# Processor_Interface.net
KiCad netlist of a schematic drawn in Altium Designer
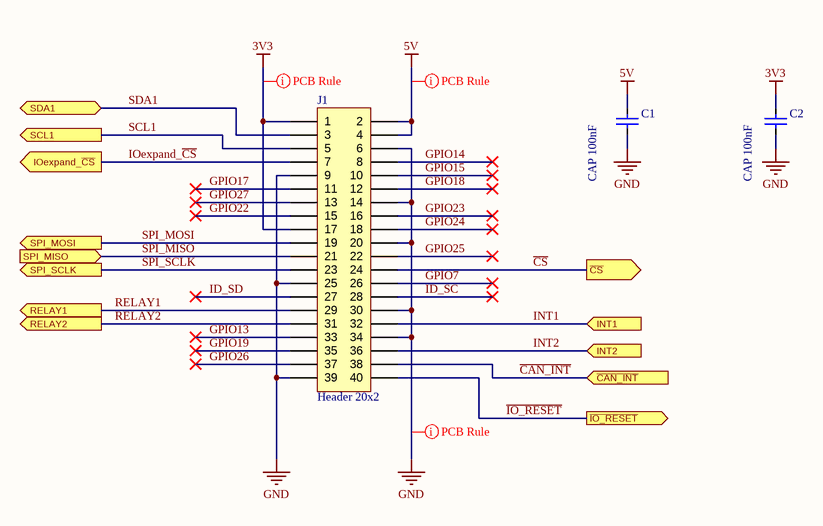
[diagram p0:  Processor_Interface.SchDoc]

(export (version "E")
  (design (tool "Eeschema 10.0.6"))
  (components
    (comp (ref "C1")
      (value "CAP 100nF")
      (footprint "0603C_L")
      (fields
        (field (name "MANUFACTURER") "Yageo")
        (field (name "MANUFACTURER PART NUMBER") "CC0603ZRY5V9BB104")
      )
      (libsource (lib "MHH -  Altium Advanced Course A365 01") (part "CMP-00119-2"))
    )
    (comp (ref "C2")
      (value "CAP 100nF")
      (footprint "0603C_L")
      (fields
        (field (name "MANUFACTURER") "Yageo")
        (field (name "MANUFACTURER PART NUMBER") "CC0603ZRY5V9BB104")
      )
      (libsource (lib "MHH -  Altium Advanced Course A365 01") (part "CMP-00119-2"))
    )
    (comp (ref "J1")
      (value "Header 20x2")
      (footprint "HDR2X20")
      (description "Header, 20-Pin, Dual row")
      (fields (field (name "PUBLISHER") "Altium Limited") (field (name "SOURCE") "WCT.SchLib"))
      (libsource (lib "MHH -  Altium Advanced Course A365 01") (part "Header 20x2"))
    )
  )
  (nets
    (net (code "1") (name "/CAN_INT") (class "Default")
      (node (ref "J1") (pin "38") (pinfunction "38_38") (pintype "passive"))
    )
    (net (code "2") (name "/GPIO7") (class "Default")
      (node (ref "J1") (pin "26") (pinfunction "26_26") (pintype "passive+no_connect"))
    )
    (net (code "3") (name "/GPIO13") (class "Default")
      (node (ref "J1") (pin "33") (pinfunction "33_33") (pintype "passive+no_connect"))
    )
    (net (code "4") (name "/GPIO14") (class "Default")
      (node (ref "J1") (pin "8") (pinfunction "8_8") (pintype "passive+no_connect"))
    )
    (net (code "5") (name "/GPIO15") (class "Default")
      (node (ref "J1") (pin "10") (pinfunction "10_10") (pintype "passive+no_connect"))
    )
    (net (code "6") (name "/GPIO17") (class "Default")
      (node (ref "J1") (pin "11") (pinfunction "11_11") (pintype "passive+no_connect"))
    )
    (net (code "7") (name "/GPIO18") (class "Default")
      (node (ref "J1") (pin "12") (pinfunction "12_12") (pintype "passive+no_connect"))
    )
    (net (code "8") (name "/GPIO19") (class "Default")
      (node (ref "J1") (pin "35") (pinfunction "35_35") (pintype "passive+no_connect"))
    )
    (net (code "9") (name "/GPIO22") (class "Default")
      (node (ref "J1") (pin "15") (pinfunction "15_15") (pintype "passive+no_connect"))
    )
    (net (code "10") (name "/GPIO23") (class "Default")
      (node (ref "J1") (pin "16") (pinfunction "16_16") (pintype "passive+no_connect"))
    )
    (net (code "11") (name "/GPIO24") (class "Default")
      (node (ref "J1") (pin "18") (pinfunction "18_18") (pintype "passive+no_connect"))
    )
    (net (code "12") (name "/GPIO25") (class "Default")
      (node (ref "J1") (pin "22") (pinfunction "22_22") (pintype "passive+no_connect"))
    )
    (net (code "13") (name "/GPIO26") (class "Default")
      (node (ref "J1") (pin "37") (pinfunction "37_37") (pintype "passive+no_connect"))
    )
    (net (code "14") (name "/GPIO27") (class "Default")
      (node (ref "J1") (pin "13") (pinfunction "13_13") (pintype "passive+no_connect"))
    )
    (net (code "15") (name "/ID_SC") (class "Default")
      (node (ref "J1") (pin "28") (pinfunction "28_28") (pintype "passive+no_connect"))
    )
    (net (code "16") (name "/ID_SD") (class "Default")
      (node (ref "J1") (pin "27") (pinfunction "27_27") (pintype "passive+no_connect"))
    )
    (net (code "17") (name "/INT1") (class "Default")
      (node (ref "J1") (pin "32") (pinfunction "32_32") (pintype "passive"))
    )
    (net (code "18") (name "/INT2") (class "Default")
      (node (ref "J1") (pin "36") (pinfunction "36_36") (pintype "passive"))
    )
    (net (code "19") (name "/IO_RESET") (class "Default")
      (node (ref "J1") (pin "40") (pinfunction "40_40") (pintype "passive"))
    )
    (net (code "20") (name "/IOexpand_~{CS}") (class "Default")
      (node (ref "J1") (pin "7") (pinfunction "7_7") (pintype "passive"))
    )
    (net (code "21") (name "/RELAY1") (class "Default")
      (node (ref "J1") (pin "29") (pinfunction "29_29") (pintype "passive"))
    )
    (net (code "22") (name "/RELAY2") (class "Default")
      (node (ref "J1") (pin "31") (pinfunction "31_31") (pintype "passive"))
    )
    (net (code "23") (name "/SCL1") (class "Default")
      (node (ref "J1") (pin "5") (pinfunction "5_5") (pintype "passive"))
    )
    (net (code "24") (name "/SDA1") (class "Default")
      (node (ref "J1") (pin "3") (pinfunction "3_3") (pintype "passive"))
    )
    (net (code "25") (name "/SPI_MISO") (class "Default")
      (node (ref "J1") (pin "21") (pinfunction "21_21") (pintype "passive"))
    )
    (net (code "26") (name "/SPI_MOSI") (class "Default")
      (node (ref "J1") (pin "19") (pinfunction "19_19") (pintype "passive"))
    )
    (net (code "27") (name "/SPI_SCLK") (class "Default")
      (node (ref "J1") (pin "23") (pinfunction "23_23") (pintype "passive"))
    )
    (net (code "28") (name "/~{CS}") (class "Default")
      (node (ref "J1") (pin "24") (pinfunction "24_24") (pintype "passive"))
    )
    (net (code "29") (name "3V3") (class "Default")
      (node (ref "C2") (pin "2") (pinfunction "2_2") (pintype "passive"))
      (node (ref "J1") (pin "1") (pinfunction "1_1") (pintype "passive"))
      (node (ref "J1") (pin "17") (pinfunction "17_17") (pintype "passive"))
    )
    (net (code "30") (name "5V") (class "Default")
      (node (ref "C1") (pin "2") (pinfunction "2_2") (pintype "passive"))
      (node (ref "J1") (pin "2") (pinfunction "2_2") (pintype "passive"))
      (node (ref "J1") (pin "4") (pinfunction "4_4") (pintype "passive"))
    )
    (net (code "31") (name "GND") (class "Default")
      (node (ref "C1") (pin "1") (pinfunction "1_1") (pintype "passive"))
      (node (ref "C2") (pin "1") (pinfunction "1_1") (pintype "passive"))
      (node (ref "J1") (pin "14") (pinfunction "14_14") (pintype "passive"))
      (node (ref "J1") (pin "20") (pinfunction "20_20") (pintype "passive"))
      (node (ref "J1") (pin "25") (pinfunction "25_25") (pintype "passive"))
      (node (ref "J1") (pin "30") (pinfunction "30_30") (pintype "passive"))
      (node (ref "J1") (pin "34") (pinfunction "34_34") (pintype "passive"))
      (node (ref "J1") (pin "39") (pinfunction "39_39") (pintype "passive"))
      (node (ref "J1") (pin "6") (pinfunction "6_6") (pintype "passive"))
      (node (ref "J1") (pin "9") (pinfunction "9_9") (pintype "passive"))
    )
  )
)
